# RFID_Controller.net
KiCad netlist of a schematic drawn in EAGLE
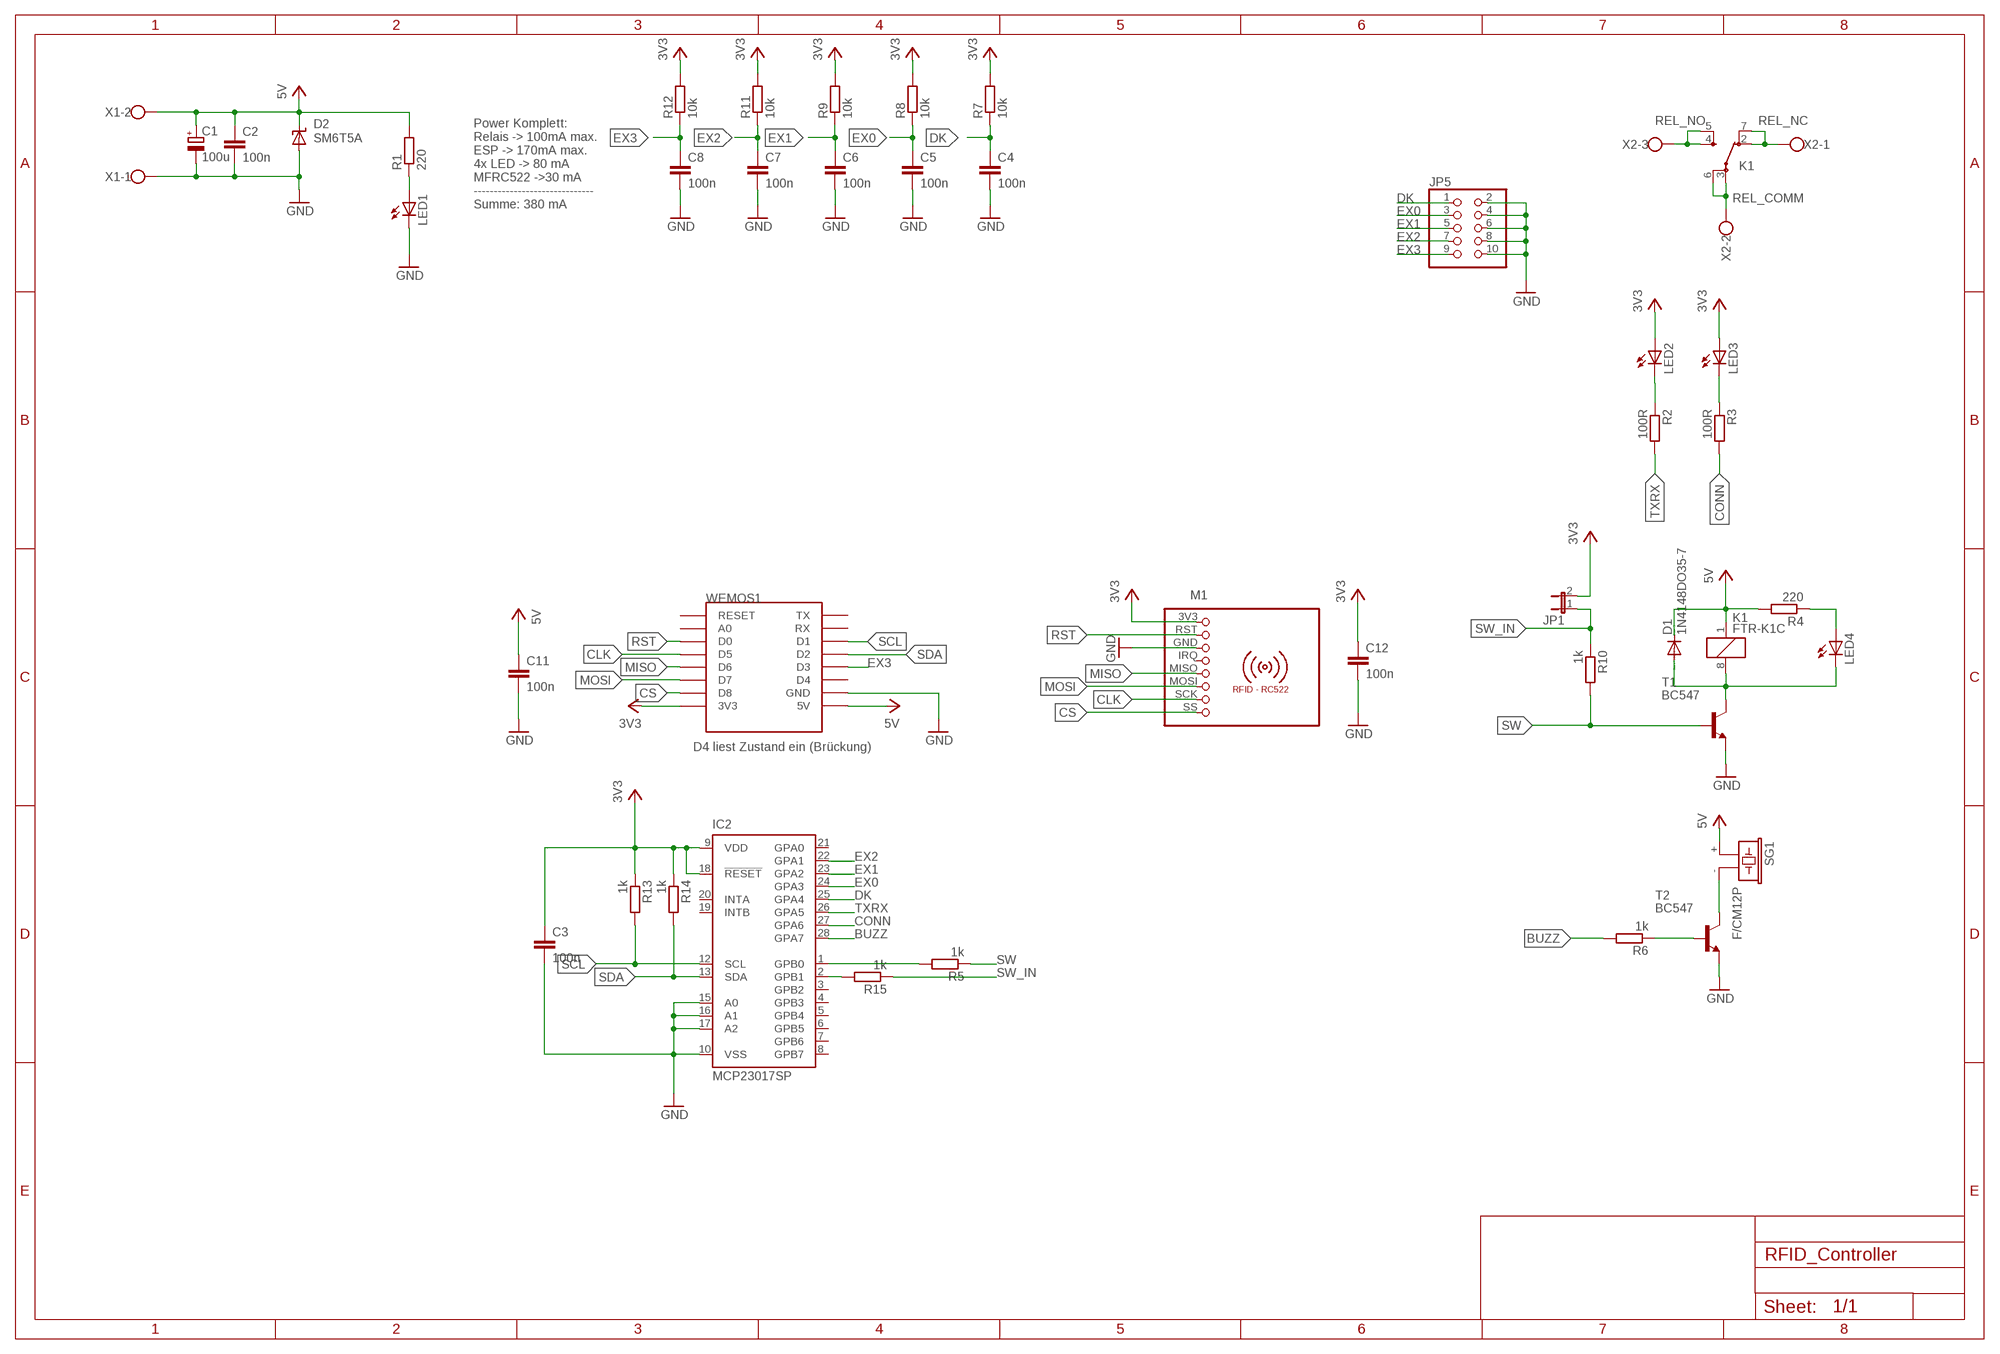
[diagram p0: schematic, sheet 1]

(export (version "E")
  (design (tool "Eeschema 10.0.6"))
  (components
    (comp (ref "C1")
      (value "100u")
      (footprint "eagle-import:E2,5-7")
      (libsource (lib "eagle-import") (part "CPOL-EUE2.5-7"))
    )
    (comp (ref "C2")
      (value "100n")
      (footprint "eagle-import:C050-025X075")
      (libsource (lib "eagle-import") (part "C-EU050-025X075"))
    )
    (comp (ref "C3")
      (value "100n")
      (footprint "eagle-import:C050-025X075")
      (libsource (lib "eagle-import") (part "C-EU050-025X075"))
    )
    (comp (ref "C4")
      (value "100n")
      (footprint "eagle-import:C050-025X075")
      (libsource (lib "eagle-import") (part "C-EU050-025X075"))
    )
    (comp (ref "C5")
      (value "100n")
      (footprint "eagle-import:C050-025X075")
      (libsource (lib "eagle-import") (part "C-EU050-025X075"))
    )
    (comp (ref "C6")
      (value "100n")
      (footprint "eagle-import:C050-025X075")
      (libsource (lib "eagle-import") (part "C-EU050-025X075"))
    )
    (comp (ref "C7")
      (value "100n")
      (footprint "eagle-import:C050-025X075")
      (libsource (lib "eagle-import") (part "C-EU050-025X075"))
    )
    (comp (ref "C8")
      (value "100n")
      (footprint "eagle-import:C050-025X075")
      (libsource (lib "eagle-import") (part "C-EU050-025X075"))
    )
    (comp (ref "C11")
      (value "100n")
      (footprint "eagle-import:C050-025X075")
      (libsource (lib "eagle-import") (part "C-EU050-025X075"))
    )
    (comp (ref "C12")
      (value "100n")
      (footprint "eagle-import:C050-025X075")
      (libsource (lib "eagle-import") (part "C-EU050-025X075"))
    )
    (comp (ref "D1")
      (value "1N4148DO35-7")
      (footprint "eagle-import:DO35-7")
      (libsource (lib "eagle-import") (part "1N4148DO35-7"))
    )
    (comp (ref "D2")
      (value "SM6T5A")
      (footprint "eagle-import:SMBJ")
      (libsource (lib "eagle-import") (part "SUPPRESSOR-SMBJ"))
    )
    (comp (ref "IC2")
      (value "MCP23017SP")
      (footprint "eagle-import:DIL28-3")
      (fields (field (name "MF") "MICROCHIP") (field (name "MPN") "MCP23017-E/SP"))
      (libsource (lib "eagle-import") (part "MCP23017SP"))
    )
    (comp (ref "JP1")
      (value "JP1E")
      (footprint "eagle-import:JP1")
      (libsource (lib "eagle-import") (part "JP1E"))
    )
    (comp (ref "JP5")
      (value "PINHD-2X5")
      (footprint "eagle-import:2X05")
      (libsource (lib "eagle-import") (part "PINHD-2X5"))
    )
    (comp (ref "K1")
      (value "FTR-K1C")
      (footprint "eagle-import:FTR-K1C")
      (libsource (lib "eagle-import") (part "FTR-K1C"))
    )
    (comp (ref "LED1")
      (value "LED3MM")
      (footprint "eagle-import:LED3MM")
      (libsource (lib "eagle-import") (part "LED3MM"))
    )
    (comp (ref "LED2")
      (value "LED3MM")
      (footprint "eagle-import:LED3MM")
      (libsource (lib "eagle-import") (part "LED3MM"))
    )
    (comp (ref "LED3")
      (value "LED3MM")
      (footprint "eagle-import:LED3MM")
      (libsource (lib "eagle-import") (part "LED3MM"))
    )
    (comp (ref "LED4")
      (value "LED3MM")
      (footprint "eagle-import:LED3MM")
      (libsource (lib "eagle-import") (part "LED3MM"))
    )
    (comp (ref "M1")
      (value "RFID-RC522")
      (footprint "eagle-import:RFID-RC522")
      (libsource (lib "eagle-import") (part "RFID-RC522"))
    )
    (comp (ref "R1")
      (value "220")
      (footprint "eagle-import:0204_7")
      (libsource (lib "eagle-import") (part "R-EU_0204/7"))
    )
    (comp (ref "R2")
      (value "100R")
      (footprint "eagle-import:0204_7")
      (libsource (lib "eagle-import") (part "R-EU_0204/7"))
    )
    (comp (ref "R3")
      (value "100R")
      (footprint "eagle-import:0204_7")
      (libsource (lib "eagle-import") (part "R-EU_0204/7"))
    )
    (comp (ref "R4")
      (value "220")
      (footprint "eagle-import:0204_7")
      (libsource (lib "eagle-import") (part "R-EU_0204/7"))
    )
    (comp (ref "R5")
      (value "1k")
      (footprint "eagle-import:0204_7")
      (libsource (lib "eagle-import") (part "R-EU_0204/7"))
    )
    (comp (ref "R6")
      (value "1k")
      (footprint "eagle-import:0204_7")
      (libsource (lib "eagle-import") (part "R-EU_0204/7"))
    )
    (comp (ref "R7")
      (value "10k")
      (footprint "eagle-import:0204_7")
      (libsource (lib "eagle-import") (part "R-EU_0204/7"))
    )
    (comp (ref "R8")
      (value "10k")
      (footprint "eagle-import:0204_7")
      (libsource (lib "eagle-import") (part "R-EU_0204/7"))
    )
    (comp (ref "R9")
      (value "10k")
      (footprint "eagle-import:0204_7")
      (libsource (lib "eagle-import") (part "R-EU_0204/7"))
    )
    (comp (ref "R10")
      (value "1k")
      (footprint "eagle-import:0204_7")
      (libsource (lib "eagle-import") (part "R-EU_0204/7"))
    )
    (comp (ref "R11")
      (value "10k")
      (footprint "eagle-import:0204_7")
      (libsource (lib "eagle-import") (part "R-EU_0204/7"))
    )
    (comp (ref "R12")
      (value "10k")
      (footprint "eagle-import:0204_7")
      (libsource (lib "eagle-import") (part "R-EU_0204/7"))
    )
    (comp (ref "R13")
      (value "1k")
      (footprint "eagle-import:0204_7")
      (libsource (lib "eagle-import") (part "R-EU_0204/7"))
    )
    (comp (ref "R14")
      (value "1k")
      (footprint "eagle-import:0204_7")
      (libsource (lib "eagle-import") (part "R-EU_0204/7"))
    )
    (comp (ref "R15")
      (value "1k")
      (footprint "eagle-import:0204_7")
      (libsource (lib "eagle-import") (part "R-EU_0204/7"))
    )
    (comp (ref "SG1")
      (value "F/CM12P")
      (footprint "eagle-import:F_CM12P")
      (libsource (lib "eagle-import") (part "F/CM12P"))
    )
    (comp (ref "T1")
      (value "BC547")
      (footprint "eagle-import:TO92")
      (libsource (lib "eagle-import") (part "BC547"))
    )
    (comp (ref "T2")
      (value "BC547")
      (footprint "eagle-import:TO92")
      (libsource (lib "eagle-import") (part "BC547"))
    )
    (comp (ref "WEMOS1")
      (value "WEMOS-D1-MINI")
      (footprint "eagle-import:WEMOS-D1-MINI")
      (libsource (lib "eagle-import") (part "WEMOS-D1-MINI"))
    )
    (comp (ref "X1")
      (value "W237-102")
      (footprint "eagle-import:W237-102")
      (fields (field (name "MPN") "237-102"))
      (libsource (lib "eagle-import") (part "W237-102"))
    )
    (comp (ref "X2")
      (value "W237-103")
      (footprint "eagle-import:W237-103")
      (fields (field (name "MPN") "237-103"))
      (libsource (lib "eagle-import") (part "W237-103"))
    )
  )
  (nets
    (net (code "1") (name "/REL_COMM") (class "Default")
      (node (ref "K1") (pin "3") (pinfunction "PA_3") (pintype "passive"))
      (node (ref "K1") (pin "6") (pinfunction "PB_6") (pintype "passive"))
      (node (ref "X2") (pin "2") (pinfunction "KL_2") (pintype "passive"))
    )
    (net (code "2") (name "/REL_NC") (class "Default")
      (node (ref "K1") (pin "2") (pinfunction "OA_2") (pintype "passive"))
      (node (ref "K1") (pin "7") (pinfunction "OB_7") (pintype "passive"))
      (node (ref "X2") (pin "1") (pinfunction "KL_1") (pintype "passive"))
    )
    (net (code "3") (name "/REL_NO") (class "Default")
      (node (ref "K1") (pin "4") (pinfunction "SA_4") (pintype "passive"))
      (node (ref "K1") (pin "5") (pinfunction "SB_5") (pintype "passive"))
      (node (ref "X2") (pin "3") (pinfunction "KL_3") (pintype "passive"))
    )
    (net (code "4") (name "3V3") (class "Default")
      (node (ref "C12") (pin "1") (pinfunction "1_1") (pintype "passive"))
      (node (ref "C3") (pin "1") (pinfunction "1_1") (pintype "passive"))
      (node (ref "IC2") (pin "18") (pinfunction "~{RESET}_18") (pintype "input"))
      (node (ref "IC2") (pin "9") (pinfunction "VDD_9") (pintype "power_in"))
      (node (ref "JP1") (pin "2") (pinfunction "2_2") (pintype "passive"))
      (node (ref "LED2") (pin "A") (pinfunction "A_A") (pintype "passive"))
      (node (ref "LED3") (pin "A") (pinfunction "A_A") (pintype "passive"))
      (node (ref "M1") (pin "3V3") (pinfunction "1_3V3") (pintype "passive"))
      (node (ref "R11") (pin "2") (pinfunction "2_2") (pintype "passive"))
      (node (ref "R12") (pin "2") (pinfunction "2_2") (pintype "passive"))
      (node (ref "R13") (pin "1") (pinfunction "1_1") (pintype "passive"))
      (node (ref "R14") (pin "1") (pinfunction "1_1") (pintype "passive"))
      (node (ref "R7") (pin "2") (pinfunction "2_2") (pintype "passive"))
      (node (ref "R8") (pin "2") (pinfunction "2_2") (pintype "passive"))
      (node (ref "R9") (pin "2") (pinfunction "2_2") (pintype "passive"))
      (node (ref "WEMOS1") (pin "3V3") (pinfunction "3V3_3V3") (pintype "bidirectional"))
    )
    (net (code "5") (name "5V") (class "Default")
      (node (ref "C1") (pin "+") (pinfunction "+_+") (pintype "passive"))
      (node (ref "C11") (pin "1") (pinfunction "1_1") (pintype "passive"))
      (node (ref "C2") (pin "1") (pinfunction "1_1") (pintype "passive"))
      (node (ref "D1") (pin "C") (pinfunction "C_C") (pintype "passive"))
      (node (ref "D2") (pin "C") (pinfunction "C_C") (pintype "passive"))
      (node (ref "K1") (pin "1") (pinfunction "1_1") (pintype "passive"))
      (node (ref "R1") (pin "2") (pinfunction "2_2") (pintype "passive"))
      (node (ref "R4") (pin "2") (pinfunction "2_2") (pintype "passive"))
      (node (ref "SG1") (pin "+") (pinfunction "1_+") (pintype "passive"))
      (node (ref "WEMOS1") (pin "5V") (pinfunction "5V_5V") (pintype "bidirectional"))
      (node (ref "X1") (pin "2") (pinfunction "KL_2") (pintype "passive"))
    )
    (net (code "6") (name "BUZZ") (class "Default")
      (node (ref "IC2") (pin "28") (pinfunction "GPA7_28") (pintype "bidirectional"))
      (node (ref "R6") (pin "2") (pinfunction "2_2") (pintype "passive"))
    )
    (net (code "7") (name "CLK") (class "Default")
      (node (ref "M1") (pin "SCK") (pinfunction "7_SCK") (pintype "passive"))
      (node (ref "WEMOS1") (pin "D5") (pinfunction "D5_D5") (pintype "bidirectional"))
    )
    (net (code "8") (name "CONN") (class "Default")
      (node (ref "IC2") (pin "27") (pinfunction "GPA6_27") (pintype "bidirectional"))
      (node (ref "R3") (pin "2") (pinfunction "2_2") (pintype "passive"))
    )
    (net (code "9") (name "CS") (class "Default")
      (node (ref "M1") (pin "SS") (pinfunction "8_SS") (pintype "passive"))
      (node (ref "WEMOS1") (pin "D8") (pinfunction "D8_D8") (pintype "bidirectional"))
    )
    (net (code "10") (name "DK") (class "Default")
      (node (ref "C4") (pin "1") (pinfunction "1_1") (pintype "passive"))
      (node (ref "IC2") (pin "25") (pinfunction "GPA4_25") (pintype "bidirectional"))
      (node (ref "JP5") (pin "1") (pinfunction "1_1") (pintype "passive"))
      (node (ref "R7") (pin "1") (pinfunction "1_1") (pintype "passive"))
    )
    (net (code "11") (name "EX0") (class "Default")
      (node (ref "C5") (pin "1") (pinfunction "1_1") (pintype "passive"))
      (node (ref "IC2") (pin "24") (pinfunction "GPA3_24") (pintype "bidirectional"))
      (node (ref "JP5") (pin "3") (pinfunction "3_3") (pintype "passive"))
      (node (ref "R8") (pin "1") (pinfunction "1_1") (pintype "passive"))
    )
    (net (code "12") (name "EX1") (class "Default")
      (node (ref "C6") (pin "1") (pinfunction "1_1") (pintype "passive"))
      (node (ref "IC2") (pin "23") (pinfunction "GPA2_23") (pintype "bidirectional"))
      (node (ref "JP5") (pin "5") (pinfunction "5_5") (pintype "passive"))
      (node (ref "R9") (pin "1") (pinfunction "1_1") (pintype "passive"))
    )
    (net (code "13") (name "EX2") (class "Default")
      (node (ref "C7") (pin "1") (pinfunction "1_1") (pintype "passive"))
      (node (ref "IC2") (pin "22") (pinfunction "GPA1_22") (pintype "bidirectional"))
      (node (ref "JP5") (pin "7") (pinfunction "7_7") (pintype "passive"))
      (node (ref "R11") (pin "1") (pinfunction "1_1") (pintype "passive"))
    )
    (net (code "14") (name "EX3") (class "Default")
      (node (ref "C8") (pin "1") (pinfunction "1_1") (pintype "passive"))
      (node (ref "JP5") (pin "9") (pinfunction "9_9") (pintype "passive"))
      (node (ref "R12") (pin "1") (pinfunction "1_1") (pintype "passive"))
      (node (ref "WEMOS1") (pin "D3") (pinfunction "D3_D3") (pintype "bidirectional"))
    )
    (net (code "15") (name "GND") (class "Default")
      (node (ref "C1") (pin "-") (pinfunction "-_-") (pintype "passive"))
      (node (ref "C11") (pin "2") (pinfunction "2_2") (pintype "passive"))
      (node (ref "C12") (pin "2") (pinfunction "2_2") (pintype "passive"))
      (node (ref "C2") (pin "2") (pinfunction "2_2") (pintype "passive"))
      (node (ref "C3") (pin "2") (pinfunction "2_2") (pintype "passive"))
      (node (ref "C4") (pin "2") (pinfunction "2_2") (pintype "passive"))
      (node (ref "C5") (pin "2") (pinfunction "2_2") (pintype "passive"))
      (node (ref "C6") (pin "2") (pinfunction "2_2") (pintype "passive"))
      (node (ref "C7") (pin "2") (pinfunction "2_2") (pintype "passive"))
      (node (ref "C8") (pin "2") (pinfunction "2_2") (pintype "passive"))
      (node (ref "D2") (pin "A") (pinfunction "A_A") (pintype "passive"))
      (node (ref "IC2") (pin "10") (pinfunction "VSS_10") (pintype "power_in"))
      (node (ref "IC2") (pin "15") (pinfunction "A0_15") (pintype "input"))
      (node (ref "IC2") (pin "16") (pinfunction "A1_16") (pintype "input"))
      (node (ref "IC2") (pin "17") (pinfunction "A2_17") (pintype "input"))
      (node (ref "JP5") (pin "10") (pinfunction "10_10") (pintype "passive"))
      (node (ref "JP5") (pin "2") (pinfunction "2_2") (pintype "passive"))
      (node (ref "JP5") (pin "4") (pinfunction "4_4") (pintype "passive"))
      (node (ref "JP5") (pin "6") (pinfunction "6_6") (pintype "passive"))
      (node (ref "JP5") (pin "8") (pinfunction "8_8") (pintype "passive"))
      (node (ref "LED1") (pin "K") (pinfunction "C_K") (pintype "passive"))
      (node (ref "M1") (pin "GND") (pinfunction "3_GND") (pintype "passive"))
      (node (ref "T1") (pin "1") (pinfunction "E_1") (pintype "passive"))
      (node (ref "T2") (pin "1") (pinfunction "E_1") (pintype "passive"))
      (node (ref "WEMOS1") (pin "GND") (pinfunction "GND_GND") (pintype "bidirectional"))
      (node (ref "X1") (pin "1") (pinfunction "KL_1") (pintype "passive"))
    )
    (net (code "16") (name "MISO") (class "Default")
      (node (ref "M1") (pin "MISO") (pinfunction "5_MISO") (pintype "passive"))
      (node (ref "WEMOS1") (pin "D6") (pinfunction "D6_D6") (pintype "bidirectional"))
    )
    (net (code "17") (name "MOSI") (class "Default")
      (node (ref "M1") (pin "MOSI") (pinfunction "6_MOSI") (pintype "passive"))
      (node (ref "WEMOS1") (pin "D7") (pinfunction "D7_D7") (pintype "bidirectional"))
    )
    (net (code "18") (name "Net-(IC2-GPB0)") (class "Default")
      (node (ref "IC2") (pin "1") (pinfunction "GPB0_1") (pintype "bidirectional"))
      (node (ref "R5") (pin "2") (pinfunction "2_2") (pintype "passive"))
    )
    (net (code "19") (name "Net-(IC2-GPB1)") (class "Default")
      (node (ref "IC2") (pin "2") (pinfunction "GPB1_2") (pintype "bidirectional"))
      (node (ref "R15") (pin "2") (pinfunction "2_2") (pintype "passive"))
    )
    (net (code "20") (name "Net-(K1B-2)") (class "Default")
      (node (ref "D1") (pin "A") (pinfunction "A_A") (pintype "passive"))
      (node (ref "K1") (pin "8") (pinfunction "2_8") (pintype "passive"))
      (node (ref "LED4") (pin "K") (pinfunction "C_K") (pintype "passive"))
      (node (ref "T1") (pin "3") (pinfunction "C_3") (pintype "passive"))
    )
    (net (code "21") (name "Net-(LED1-PadA)") (class "Default")
      (node (ref "LED1") (pin "A") (pinfunction "A_A") (pintype "passive"))
      (node (ref "R1") (pin "1") (pinfunction "1_1") (pintype "passive"))
    )
    (net (code "22") (name "Net-(LED2-C)") (class "Default")
      (node (ref "LED2") (pin "K") (pinfunction "C_K") (pintype "passive"))
      (node (ref "R2") (pin "1") (pinfunction "1_1") (pintype "passive"))
    )
    (net (code "23") (name "Net-(LED3-C)") (class "Default")
      (node (ref "LED3") (pin "K") (pinfunction "C_K") (pintype "passive"))
      (node (ref "R3") (pin "1") (pinfunction "1_1") (pintype "passive"))
    )
    (net (code "24") (name "Net-(LED4-PadA)") (class "Default")
      (node (ref "LED4") (pin "A") (pinfunction "A_A") (pintype "passive"))
      (node (ref "R4") (pin "1") (pinfunction "1_1") (pintype "passive"))
    )
    (net (code "25") (name "Net-(SG1-2)") (class "Default")
      (node (ref "SG1") (pin "-") (pinfunction "2_-") (pintype "passive"))
      (node (ref "T2") (pin "3") (pinfunction "C_3") (pintype "passive"))
    )
    (net (code "26") (name "Net-(T2-B)") (class "Default")
      (node (ref "R6") (pin "1") (pinfunction "1_1") (pintype "passive"))
      (node (ref "T2") (pin "2") (pinfunction "B_2") (pintype "passive"))
    )
    (net (code "27") (name "RST") (class "Default")
      (node (ref "M1") (pin "RST") (pinfunction "2_RST") (pintype "passive"))
      (node (ref "WEMOS1") (pin "D0") (pinfunction "D0_D0") (pintype "bidirectional"))
    )
    (net (code "28") (name "SCL") (class "Default")
      (node (ref "IC2") (pin "12") (pinfunction "SCL_12") (pintype "input"))
      (node (ref "R13") (pin "2") (pinfunction "2_2") (pintype "passive"))
      (node (ref "WEMOS1") (pin "D1") (pinfunction "D1_D1") (pintype "bidirectional"))
    )
    (net (code "29") (name "SDA") (class "Default")
      (node (ref "IC2") (pin "13") (pinfunction "SDA_13") (pintype "bidirectional"))
      (node (ref "R14") (pin "2") (pinfunction "2_2") (pintype "passive"))
      (node (ref "WEMOS1") (pin "D2") (pinfunction "D2_D2") (pintype "bidirectional"))
    )
    (net (code "30") (name "SW") (class "Default")
      (node (ref "R10") (pin "2") (pinfunction "2_2") (pintype "passive"))
      (node (ref "R5") (pin "1") (pinfunction "1_1") (pintype "passive"))
      (node (ref "T1") (pin "2") (pinfunction "B_2") (pintype "passive"))
    )
    (net (code "31") (name "SW_IN") (class "Default")
      (node (ref "JP1") (pin "1") (pinfunction "1_1") (pintype "passive"))
      (node (ref "R10") (pin "1") (pinfunction "1_1") (pintype "passive"))
      (node (ref "R15") (pin "1") (pinfunction "1_1") (pintype "passive"))
    )
    (net (code "32") (name "TXRX") (class "Default")
      (node (ref "IC2") (pin "26") (pinfunction "GPA5_26") (pintype "bidirectional"))
      (node (ref "R2") (pin "2") (pinfunction "2_2") (pintype "passive"))
    )
    (net (code "33") (name "unconnected-(IC2-GPA0-Pad21)") (class "Default")
      (node (ref "IC2") (pin "21") (pinfunction "GPA0_21") (pintype "bidirectional"))
    )
    (net (code "34") (name "unconnected-(IC2-GPB2-Pad3)") (class "Default")
      (node (ref "IC2") (pin "3") (pinfunction "GPB2_3") (pintype "bidirectional"))
    )
    (net (code "35") (name "unconnected-(IC2-GPB3-Pad4)") (class "Default")
      (node (ref "IC2") (pin "4") (pinfunction "GPB3_4") (pintype "bidirectional"))
    )
    (net (code "36") (name "unconnected-(IC2-GPB4-Pad5)") (class "Default")
      (node (ref "IC2") (pin "5") (pinfunction "GPB4_5") (pintype "bidirectional"))
    )
    (net (code "37") (name "unconnected-(IC2-GPB5-Pad6)") (class "Default")
      (node (ref "IC2") (pin "6") (pinfunction "GPB5_6") (pintype "bidirectional"))
    )
    (net (code "38") (name "unconnected-(IC2-GPB6-Pad7)") (class "Default")
      (node (ref "IC2") (pin "7") (pinfunction "GPB6_7") (pintype "bidirectional"))
    )
    (net (code "39") (name "unconnected-(IC2-GPB7-Pad8)") (class "Default")
      (node (ref "IC2") (pin "8") (pinfunction "GPB7_8") (pintype "bidirectional"))
    )
    (net (code "40") (name "unconnected-(IC2-INTA-Pad20)") (class "Default")
      (node (ref "IC2") (pin "20") (pinfunction "INTA_20") (pintype "output"))
    )
    (net (code "41") (name "unconnected-(IC2-INTB-Pad19)") (class "Default")
      (node (ref "IC2") (pin "19") (pinfunction "INTB_19") (pintype "output"))
    )
    (net (code "42") (name "unconnected-(M1-4-PadIRQ)") (class "Default")
      (node (ref "M1") (pin "IRQ") (pinfunction "4_IRQ") (pintype "passive"))
    )
    (net (code "43") (name "unconnected-(WEMOS1-PadA0)") (class "Default")
      (node (ref "WEMOS1") (pin "A0") (pinfunction "A0_A0") (pintype "bidirectional"))
    )
    (net (code "44") (name "unconnected-(WEMOS1-PadD4)") (class "Default")
      (node (ref "WEMOS1") (pin "D4") (pinfunction "D4_D4") (pintype "bidirectional"))
    )
    (net (code "45") (name "unconnected-(WEMOS1-PadRESET)") (class "Default")
      (node (ref "WEMOS1") (pin "RESET") (pinfunction "RESET_RESET") (pintype "bidirectional"))
    )
    (net (code "46") (name "unconnected-(WEMOS1-PadRX)") (class "Default")
      (node (ref "WEMOS1") (pin "RX") (pinfunction "RX_RX") (pintype "bidirectional"))
    )
    (net (code "47") (name "unconnected-(WEMOS1-PadTX)") (class "Default")
      (node (ref "WEMOS1") (pin "TX") (pinfunction "TX_TX") (pintype "bidirectional"))
    )
  )
)
